# TopSide.net
KiCad netlist of a schematic drawn in Altium Designer
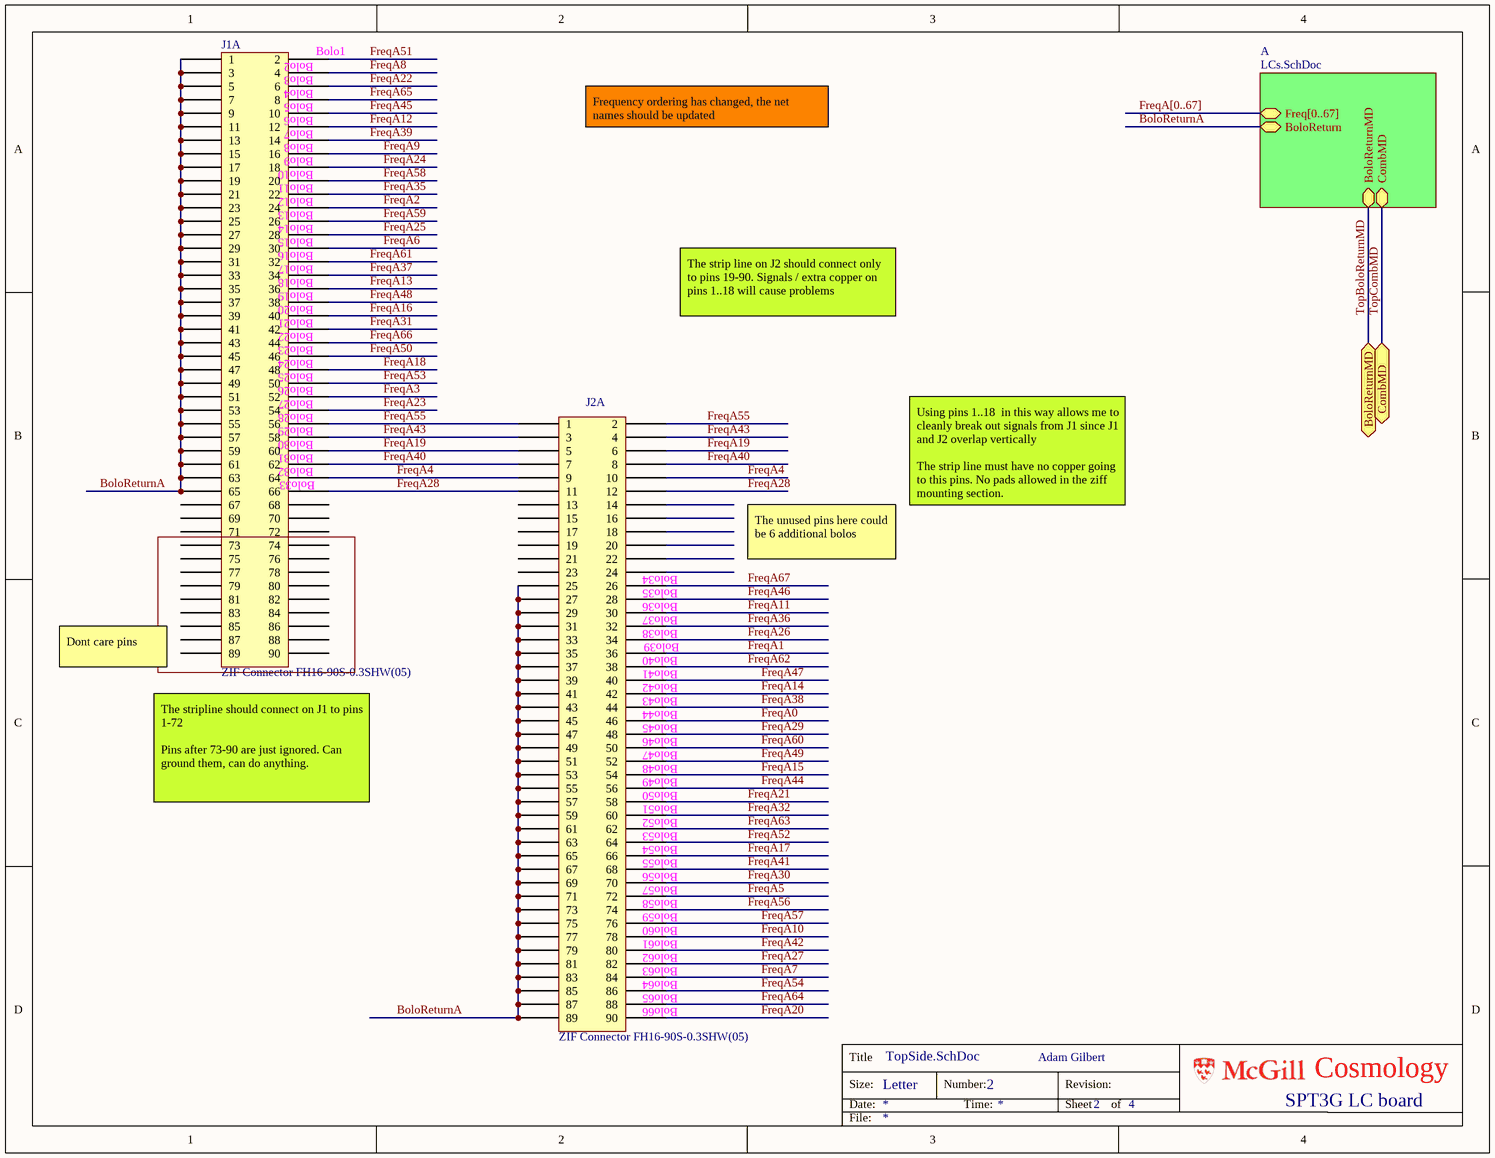
[diagram p0: TopSide.SchDoc]

(export (version "E")
  (design (tool "Eeschema 10.0.6"))
  (components
    (comp (ref "J1A")
      (value "ZIF Connector FH16-90S-0.3SHW(05)")
      (footprint "LCBoard_ZIFCon")
      (libsource (lib "SPT3G_LCBoard") (part "LCboard_FH16-90S-0.3SHW(05)"))
    )
    (comp (ref "J2A")
      (value "ZIF Connector FH16-90S-0.3SHW(05)")
      (footprint "LCBoard_ZIFCon")
      (libsource (lib "SPT3G_LCBoard") (part "LCboard_FH16-90S-0.3SHW(05)"))
    )
  )
  (nets
    (net (code "3") (name "/BoloReturnA") (class "Default")
      (node (ref "J1A") (pin "1") (pinfunction "1_1") (pintype "passive"))
      (node (ref "J1A") (pin "11") (pinfunction "11_11") (pintype "passive"))
      (node (ref "J1A") (pin "13") (pinfunction "13_13") (pintype "passive"))
      (node (ref "J1A") (pin "15") (pinfunction "15_15") (pintype "passive"))
      (node (ref "J1A") (pin "17") (pinfunction "17_17") (pintype "passive"))
      (node (ref "J1A") (pin "19") (pinfunction "19_19") (pintype "passive"))
      (node (ref "J1A") (pin "21") (pinfunction "21_21") (pintype "passive"))
      (node (ref "J1A") (pin "23") (pinfunction "23_23") (pintype "passive"))
      (node (ref "J1A") (pin "25") (pinfunction "25_25") (pintype "passive"))
      (node (ref "J1A") (pin "27") (pinfunction "27_27") (pintype "passive"))
      (node (ref "J1A") (pin "29") (pinfunction "29_29") (pintype "passive"))
      (node (ref "J1A") (pin "3") (pinfunction "3_3") (pintype "passive"))
      (node (ref "J1A") (pin "31") (pinfunction "31_31") (pintype "passive"))
      (node (ref "J1A") (pin "33") (pinfunction "33_33") (pintype "passive"))
      (node (ref "J1A") (pin "35") (pinfunction "35_35") (pintype "passive"))
      (node (ref "J1A") (pin "37") (pinfunction "37_37") (pintype "passive"))
      (node (ref "J1A") (pin "39") (pinfunction "39_39") (pintype "passive"))
      (node (ref "J1A") (pin "41") (pinfunction "41_41") (pintype "passive"))
      (node (ref "J1A") (pin "43") (pinfunction "43_43") (pintype "passive"))
      (node (ref "J1A") (pin "45") (pinfunction "45_45") (pintype "passive"))
      (node (ref "J1A") (pin "47") (pinfunction "47_47") (pintype "passive"))
      (node (ref "J1A") (pin "49") (pinfunction "49_49") (pintype "passive"))
      (node (ref "J1A") (pin "5") (pinfunction "5_5") (pintype "passive"))
      (node (ref "J1A") (pin "51") (pinfunction "51_51") (pintype "passive"))
      (node (ref "J1A") (pin "53") (pinfunction "53_53") (pintype "passive"))
      (node (ref "J1A") (pin "55") (pinfunction "55_55") (pintype "passive"))
      (node (ref "J1A") (pin "57") (pinfunction "57_57") (pintype "passive"))
      (node (ref "J1A") (pin "59") (pinfunction "59_59") (pintype "passive"))
      (node (ref "J1A") (pin "61") (pinfunction "61_61") (pintype "passive"))
      (node (ref "J1A") (pin "63") (pinfunction "63_63") (pintype "passive"))
      (node (ref "J1A") (pin "65") (pinfunction "65_65") (pintype "passive"))
      (node (ref "J1A") (pin "7") (pinfunction "7_7") (pintype "passive"))
      (node (ref "J1A") (pin "9") (pinfunction "9_9") (pintype "passive"))
      (node (ref "J2A") (pin "25") (pinfunction "25_25") (pintype "passive"))
      (node (ref "J2A") (pin "27") (pinfunction "27_27") (pintype "passive"))
      (node (ref "J2A") (pin "29") (pinfunction "29_29") (pintype "passive"))
      (node (ref "J2A") (pin "31") (pinfunction "31_31") (pintype "passive"))
      (node (ref "J2A") (pin "33") (pinfunction "33_33") (pintype "passive"))
      (node (ref "J2A") (pin "35") (pinfunction "35_35") (pintype "passive"))
      (node (ref "J2A") (pin "37") (pinfunction "37_37") (pintype "passive"))
      (node (ref "J2A") (pin "39") (pinfunction "39_39") (pintype "passive"))
      (node (ref "J2A") (pin "41") (pinfunction "41_41") (pintype "passive"))
      (node (ref "J2A") (pin "43") (pinfunction "43_43") (pintype "passive"))
      (node (ref "J2A") (pin "45") (pinfunction "45_45") (pintype "passive"))
      (node (ref "J2A") (pin "47") (pinfunction "47_47") (pintype "passive"))
      (node (ref "J2A") (pin "49") (pinfunction "49_49") (pintype "passive"))
      (node (ref "J2A") (pin "51") (pinfunction "51_51") (pintype "passive"))
      (node (ref "J2A") (pin "53") (pinfunction "53_53") (pintype "passive"))
      (node (ref "J2A") (pin "55") (pinfunction "55_55") (pintype "passive"))
      (node (ref "J2A") (pin "57") (pinfunction "57_57") (pintype "passive"))
      (node (ref "J2A") (pin "59") (pinfunction "59_59") (pintype "passive"))
      (node (ref "J2A") (pin "61") (pinfunction "61_61") (pintype "passive"))
      (node (ref "J2A") (pin "63") (pinfunction "63_63") (pintype "passive"))
      (node (ref "J2A") (pin "65") (pinfunction "65_65") (pintype "passive"))
      (node (ref "J2A") (pin "67") (pinfunction "67_67") (pintype "passive"))
      (node (ref "J2A") (pin "69") (pinfunction "69_69") (pintype "passive"))
      (node (ref "J2A") (pin "71") (pinfunction "71_71") (pintype "passive"))
      (node (ref "J2A") (pin "73") (pinfunction "73_73") (pintype "passive"))
      (node (ref "J2A") (pin "75") (pinfunction "75_75") (pintype "passive"))
      (node (ref "J2A") (pin "77") (pinfunction "77_77") (pintype "passive"))
      (node (ref "J2A") (pin "79") (pinfunction "79_79") (pintype "passive"))
      (node (ref "J2A") (pin "81") (pinfunction "81_81") (pintype "passive"))
      (node (ref "J2A") (pin "83") (pinfunction "83_83") (pintype "passive"))
      (node (ref "J2A") (pin "85") (pinfunction "85_85") (pintype "passive"))
      (node (ref "J2A") (pin "87") (pinfunction "87_87") (pintype "passive"))
      (node (ref "J2A") (pin "89") (pinfunction "89_89") (pintype "passive"))
    )
    (net (code "4") (name "/FreqA0") (class "Default")
      (node (ref "J2A") (pin "46") (pinfunction "46_46") (pintype "passive"))
    )
    (net (code "5") (name "/FreqA1") (class "Default")
      (node (ref "J2A") (pin "36") (pinfunction "36_36") (pintype "passive"))
    )
    (net (code "6") (name "/FreqA2") (class "Default")
      (node (ref "J1A") (pin "24") (pinfunction "24_24") (pintype "passive"))
    )
    (net (code "7") (name "/FreqA3") (class "Default")
      (node (ref "J1A") (pin "52") (pinfunction "52_52") (pintype "passive"))
    )
    (net (code "8") (name "/FreqA4") (class "Default")
      (node (ref "J1A") (pin "64") (pinfunction "64_64") (pintype "passive"))
      (node (ref "J2A") (pin "10") (pinfunction "10_10") (pintype "passive"))
      (node (ref "J2A") (pin "9") (pinfunction "9_9") (pintype "passive"))
    )
    (net (code "9") (name "/FreqA5") (class "Default")
      (node (ref "J2A") (pin "72") (pinfunction "72_72") (pintype "passive"))
    )
    (net (code "10") (name "/FreqA6") (class "Default")
      (node (ref "J1A") (pin "30") (pinfunction "30_30") (pintype "passive"))
    )
    (net (code "11") (name "/FreqA7") (class "Default")
      (node (ref "J2A") (pin "84") (pinfunction "84_84") (pintype "passive"))
    )
    (net (code "12") (name "/FreqA8") (class "Default")
      (node (ref "J1A") (pin "4") (pinfunction "4_4") (pintype "passive"))
    )
    (net (code "13") (name "/FreqA9") (class "Default")
      (node (ref "J1A") (pin "16") (pinfunction "16_16") (pintype "passive"))
    )
    (net (code "14") (name "/FreqA10") (class "Default")
      (node (ref "J2A") (pin "78") (pinfunction "78_78") (pintype "passive"))
    )
    (net (code "15") (name "/FreqA11") (class "Default")
      (node (ref "J2A") (pin "30") (pinfunction "30_30") (pintype "passive"))
    )
    (net (code "16") (name "/FreqA12") (class "Default")
      (node (ref "J1A") (pin "12") (pinfunction "12_12") (pintype "passive"))
    )
    (net (code "17") (name "/FreqA13") (class "Default")
      (node (ref "J1A") (pin "36") (pinfunction "36_36") (pintype "passive"))
    )
    (net (code "18") (name "/FreqA14") (class "Default")
      (node (ref "J2A") (pin "42") (pinfunction "42_42") (pintype "passive"))
    )
    (net (code "19") (name "/FreqA15") (class "Default")
      (node (ref "J2A") (pin "54") (pinfunction "54_54") (pintype "passive"))
    )
    (net (code "20") (name "/FreqA16") (class "Default")
      (node (ref "J1A") (pin "40") (pinfunction "40_40") (pintype "passive"))
    )
    (net (code "21") (name "/FreqA17") (class "Default")
      (node (ref "J2A") (pin "66") (pinfunction "66_66") (pintype "passive"))
    )
    (net (code "22") (name "/FreqA18") (class "Default")
      (node (ref "J1A") (pin "48") (pinfunction "48_48") (pintype "passive"))
    )
    (net (code "23") (name "/FreqA19") (class "Default")
      (node (ref "J1A") (pin "60") (pinfunction "60_60") (pintype "passive"))
      (node (ref "J2A") (pin "5") (pinfunction "5_5") (pintype "passive"))
      (node (ref "J2A") (pin "6") (pinfunction "6_6") (pintype "passive"))
    )
    (net (code "24") (name "/FreqA20") (class "Default")
      (node (ref "J2A") (pin "90") (pinfunction "90_90") (pintype "passive"))
    )
    (net (code "25") (name "/FreqA21") (class "Default")
      (node (ref "J2A") (pin "58") (pinfunction "58_58") (pintype "passive"))
    )
    (net (code "26") (name "/FreqA22") (class "Default")
      (node (ref "J1A") (pin "6") (pinfunction "6_6") (pintype "passive"))
    )
    (net (code "27") (name "/FreqA23") (class "Default")
      (node (ref "J1A") (pin "54") (pinfunction "54_54") (pintype "passive"))
    )
    (net (code "28") (name "/FreqA24") (class "Default")
      (node (ref "J1A") (pin "18") (pinfunction "18_18") (pintype "passive"))
    )
    (net (code "29") (name "/FreqA25") (class "Default")
      (node (ref "J1A") (pin "28") (pinfunction "28_28") (pintype "passive"))
    )
    (net (code "30") (name "/FreqA26") (class "Default")
      (node (ref "J2A") (pin "34") (pinfunction "34_34") (pintype "passive"))
    )
    (net (code "31") (name "/FreqA27") (class "Default")
      (node (ref "J2A") (pin "82") (pinfunction "82_82") (pintype "passive"))
    )
    (net (code "32") (name "/FreqA28") (class "Default")
      (node (ref "J1A") (pin "66") (pinfunction "66_66") (pintype "passive"))
      (node (ref "J2A") (pin "11") (pinfunction "11_11") (pintype "passive"))
      (node (ref "J2A") (pin "12") (pinfunction "12_12") (pintype "passive"))
    )
    (net (code "33") (name "/FreqA29") (class "Default")
      (node (ref "J2A") (pin "48") (pinfunction "48_48") (pintype "passive"))
    )
    (net (code "34") (name "/FreqA30") (class "Default")
      (node (ref "J2A") (pin "70") (pinfunction "70_70") (pintype "passive"))
    )
    (net (code "35") (name "/FreqA31") (class "Default")
      (node (ref "J1A") (pin "42") (pinfunction "42_42") (pintype "passive"))
    )
    (net (code "36") (name "/FreqA32") (class "Default")
      (node (ref "J2A") (pin "60") (pinfunction "60_60") (pintype "passive"))
    )
    (net (code "37") (name "/FreqA35") (class "Default")
      (node (ref "J1A") (pin "22") (pinfunction "22_22") (pintype "passive"))
    )
    (net (code "38") (name "/FreqA36") (class "Default")
      (node (ref "J2A") (pin "32") (pinfunction "32_32") (pintype "passive"))
    )
    (net (code "39") (name "/FreqA37") (class "Default")
      (node (ref "J1A") (pin "34") (pinfunction "34_34") (pintype "passive"))
    )
    (net (code "40") (name "/FreqA38") (class "Default")
      (node (ref "J2A") (pin "44") (pinfunction "44_44") (pintype "passive"))
    )
    (net (code "41") (name "/FreqA39") (class "Default")
      (node (ref "J1A") (pin "14") (pinfunction "14_14") (pintype "passive"))
    )
    (net (code "42") (name "/FreqA40") (class "Default")
      (node (ref "J1A") (pin "62") (pinfunction "62_62") (pintype "passive"))
      (node (ref "J2A") (pin "7") (pinfunction "7_7") (pintype "passive"))
      (node (ref "J2A") (pin "8") (pinfunction "8_8") (pintype "passive"))
    )
    (net (code "43") (name "/FreqA41") (class "Default")
      (node (ref "J2A") (pin "68") (pinfunction "68_68") (pintype "passive"))
    )
    (net (code "44") (name "/FreqA42") (class "Default")
      (node (ref "J2A") (pin "80") (pinfunction "80_80") (pintype "passive"))
    )
    (net (code "45") (name "/FreqA43") (class "Default")
      (node (ref "J1A") (pin "58") (pinfunction "58_58") (pintype "passive"))
      (node (ref "J2A") (pin "3") (pinfunction "3_3") (pintype "passive"))
      (node (ref "J2A") (pin "4") (pinfunction "4_4") (pintype "passive"))
    )
    (net (code "46") (name "/FreqA44") (class "Default")
      (node (ref "J2A") (pin "56") (pinfunction "56_56") (pintype "passive"))
    )
    (net (code "47") (name "/FreqA45") (class "Default")
      (node (ref "J1A") (pin "10") (pinfunction "10_10") (pintype "passive"))
    )
    (net (code "48") (name "/FreqA46") (class "Default")
      (node (ref "J2A") (pin "28") (pinfunction "28_28") (pintype "passive"))
    )
    (net (code "49") (name "/FreqA47") (class "Default")
      (node (ref "J2A") (pin "40") (pinfunction "40_40") (pintype "passive"))
    )
    (net (code "50") (name "/FreqA48") (class "Default")
      (node (ref "J1A") (pin "38") (pinfunction "38_38") (pintype "passive"))
    )
    (net (code "51") (name "/FreqA49") (class "Default")
      (node (ref "J2A") (pin "52") (pinfunction "52_52") (pintype "passive"))
    )
    (net (code "52") (name "/FreqA50") (class "Default")
      (node (ref "J1A") (pin "46") (pinfunction "46_46") (pintype "passive"))
    )
    (net (code "53") (name "/FreqA51") (class "Default")
      (node (ref "J1A") (pin "2") (pinfunction "2_2") (pintype "passive"))
    )
    (net (code "54") (name "/FreqA52") (class "Default")
      (node (ref "J2A") (pin "64") (pinfunction "64_64") (pintype "passive"))
    )
    (net (code "55") (name "/FreqA53") (class "Default")
      (node (ref "J1A") (pin "50") (pinfunction "50_50") (pintype "passive"))
    )
    (net (code "56") (name "/FreqA54") (class "Default")
      (node (ref "J2A") (pin "86") (pinfunction "86_86") (pintype "passive"))
    )
    (net (code "57") (name "/FreqA55") (class "Default")
      (node (ref "J1A") (pin "56") (pinfunction "56_56") (pintype "passive"))
      (node (ref "J2A") (pin "1") (pinfunction "1_1") (pintype "passive"))
      (node (ref "J2A") (pin "2") (pinfunction "2_2") (pintype "passive"))
    )
    (net (code "58") (name "/FreqA56") (class "Default")
      (node (ref "J2A") (pin "74") (pinfunction "74_74") (pintype "passive"))
    )
    (net (code "59") (name "/FreqA57") (class "Default")
      (node (ref "J2A") (pin "76") (pinfunction "76_76") (pintype "passive"))
    )
    (net (code "60") (name "/FreqA58") (class "Default")
      (node (ref "J1A") (pin "20") (pinfunction "20_20") (pintype "passive"))
    )
    (net (code "61") (name "/FreqA59") (class "Default")
      (node (ref "J1A") (pin "26") (pinfunction "26_26") (pintype "passive"))
    )
    (net (code "62") (name "/FreqA60") (class "Default")
      (node (ref "J2A") (pin "50") (pinfunction "50_50") (pintype "passive"))
    )
    (net (code "63") (name "/FreqA61") (class "Default")
      (node (ref "J1A") (pin "32") (pinfunction "32_32") (pintype "passive"))
    )
    (net (code "64") (name "/FreqA62") (class "Default")
      (node (ref "J2A") (pin "38") (pinfunction "38_38") (pintype "passive"))
    )
    (net (code "65") (name "/FreqA63") (class "Default")
      (node (ref "J2A") (pin "62") (pinfunction "62_62") (pintype "passive"))
    )
    (net (code "66") (name "/FreqA64") (class "Default")
      (node (ref "J2A") (pin "88") (pinfunction "88_88") (pintype "passive"))
    )
    (net (code "67") (name "/FreqA65") (class "Default")
      (node (ref "J1A") (pin "8") (pinfunction "8_8") (pintype "passive"))
    )
    (net (code "68") (name "/FreqA66") (class "Default")
      (node (ref "J1A") (pin "44") (pinfunction "44_44") (pintype "passive"))
    )
    (net (code "69") (name "/FreqA67") (class "Default")
      (node (ref "J2A") (pin "26") (pinfunction "26_26") (pintype "passive"))
    )
    (net (code "73") (name "unconnected-(J1A-Pad67)") (class "Default")
      (node (ref "J1A") (pin "67") (pinfunction "67_67") (pintype "passive"))
    )
    (net (code "74") (name "unconnected-(J1A-Pad68)") (class "Default")
      (node (ref "J1A") (pin "68") (pinfunction "68_68") (pintype "passive"))
    )
    (net (code "75") (name "unconnected-(J1A-Pad69)") (class "Default")
      (node (ref "J1A") (pin "69") (pinfunction "69_69") (pintype "passive"))
    )
    (net (code "76") (name "unconnected-(J1A-Pad70)") (class "Default")
      (node (ref "J1A") (pin "70") (pinfunction "70_70") (pintype "passive"))
    )
    (net (code "77") (name "unconnected-(J1A-Pad71)") (class "Default")
      (node (ref "J1A") (pin "71") (pinfunction "71_71") (pintype "passive"))
    )
    (net (code "78") (name "unconnected-(J1A-Pad72)") (class "Default")
      (node (ref "J1A") (pin "72") (pinfunction "72_72") (pintype "passive"))
    )
    (net (code "79") (name "unconnected-(J1A-Pad73)") (class "Default")
      (node (ref "J1A") (pin "73") (pinfunction "73_73") (pintype "passive"))
    )
    (net (code "80") (name "unconnected-(J1A-Pad74)") (class "Default")
      (node (ref "J1A") (pin "74") (pinfunction "74_74") (pintype "passive"))
    )
    (net (code "81") (name "unconnected-(J1A-Pad75)") (class "Default")
      (node (ref "J1A") (pin "75") (pinfunction "75_75") (pintype "passive"))
    )
    (net (code "82") (name "unconnected-(J1A-Pad76)") (class "Default")
      (node (ref "J1A") (pin "76") (pinfunction "76_76") (pintype "passive"))
    )
    (net (code "83") (name "unconnected-(J1A-Pad77)") (class "Default")
      (node (ref "J1A") (pin "77") (pinfunction "77_77") (pintype "passive"))
    )
    (net (code "84") (name "unconnected-(J1A-Pad78)") (class "Default")
      (node (ref "J1A") (pin "78") (pinfunction "78_78") (pintype "passive"))
    )
    (net (code "85") (name "unconnected-(J1A-Pad79)") (class "Default")
      (node (ref "J1A") (pin "79") (pinfunction "79_79") (pintype "passive"))
    )
    (net (code "86") (name "unconnected-(J1A-Pad80)") (class "Default")
      (node (ref "J1A") (pin "80") (pinfunction "80_80") (pintype "passive"))
    )
    (net (code "87") (name "unconnected-(J1A-Pad81)") (class "Default")
      (node (ref "J1A") (pin "81") (pinfunction "81_81") (pintype "passive"))
    )
    (net (code "88") (name "unconnected-(J1A-Pad82)") (class "Default")
      (node (ref "J1A") (pin "82") (pinfunction "82_82") (pintype "passive"))
    )
    (net (code "89") (name "unconnected-(J1A-Pad83)") (class "Default")
      (node (ref "J1A") (pin "83") (pinfunction "83_83") (pintype "passive"))
    )
    (net (code "90") (name "unconnected-(J1A-Pad84)") (class "Default")
      (node (ref "J1A") (pin "84") (pinfunction "84_84") (pintype "passive"))
    )
    (net (code "91") (name "unconnected-(J1A-Pad85)") (class "Default")
      (node (ref "J1A") (pin "85") (pinfunction "85_85") (pintype "passive"))
    )
    (net (code "92") (name "unconnected-(J1A-Pad86)") (class "Default")
      (node (ref "J1A") (pin "86") (pinfunction "86_86") (pintype "passive"))
    )
    (net (code "93") (name "unconnected-(J1A-Pad87)") (class "Default")
      (node (ref "J1A") (pin "87") (pinfunction "87_87") (pintype "passive"))
    )
    (net (code "94") (name "unconnected-(J1A-Pad88)") (class "Default")
      (node (ref "J1A") (pin "88") (pinfunction "88_88") (pintype "passive"))
    )
    (net (code "95") (name "unconnected-(J1A-Pad89)") (class "Default")
      (node (ref "J1A") (pin "89") (pinfunction "89_89") (pintype "passive"))
    )
    (net (code "96") (name "unconnected-(J1A-Pad90)") (class "Default")
      (node (ref "J1A") (pin "90") (pinfunction "90_90") (pintype "passive"))
    )
    (net (code "97") (name "unconnected-(J2A-Pad13)") (class "Default")
      (node (ref "J2A") (pin "13") (pinfunction "13_13") (pintype "passive"))
    )
    (net (code "98") (name "unconnected-(J2A-Pad14)") (class "Default")
      (node (ref "J2A") (pin "14") (pinfunction "14_14") (pintype "passive"))
    )
    (net (code "99") (name "unconnected-(J2A-Pad15)") (class "Default")
      (node (ref "J2A") (pin "15") (pinfunction "15_15") (pintype "passive"))
    )
    (net (code "100") (name "unconnected-(J2A-Pad16)") (class "Default")
      (node (ref "J2A") (pin "16") (pinfunction "16_16") (pintype "passive"))
    )
    (net (code "101") (name "unconnected-(J2A-Pad17)") (class "Default")
      (node (ref "J2A") (pin "17") (pinfunction "17_17") (pintype "passive"))
    )
    (net (code "102") (name "unconnected-(J2A-Pad18)") (class "Default")
      (node (ref "J2A") (pin "18") (pinfunction "18_18") (pintype "passive"))
    )
    (net (code "103") (name "unconnected-(J2A-Pad19)") (class "Default")
      (node (ref "J2A") (pin "19") (pinfunction "19_19") (pintype "passive"))
    )
    (net (code "104") (name "unconnected-(J2A-Pad20)") (class "Default")
      (node (ref "J2A") (pin "20") (pinfunction "20_20") (pintype "passive"))
    )
    (net (code "105") (name "unconnected-(J2A-Pad21)") (class "Default")
      (node (ref "J2A") (pin "21") (pinfunction "21_21") (pintype "passive"))
    )
    (net (code "106") (name "unconnected-(J2A-Pad22)") (class "Default")
      (node (ref "J2A") (pin "22") (pinfunction "22_22") (pintype "passive"))
    )
    (net (code "107") (name "unconnected-(J2A-Pad23)") (class "Default")
      (node (ref "J2A") (pin "23") (pinfunction "23_23") (pintype "passive"))
    )
    (net (code "108") (name "unconnected-(J2A-Pad24)") (class "Default")
      (node (ref "J2A") (pin "24") (pinfunction "24_24") (pintype "passive"))
    )
  )
)
